# power_tower_mast.net
KiCad netlist of a schematic drawn in EAGLE
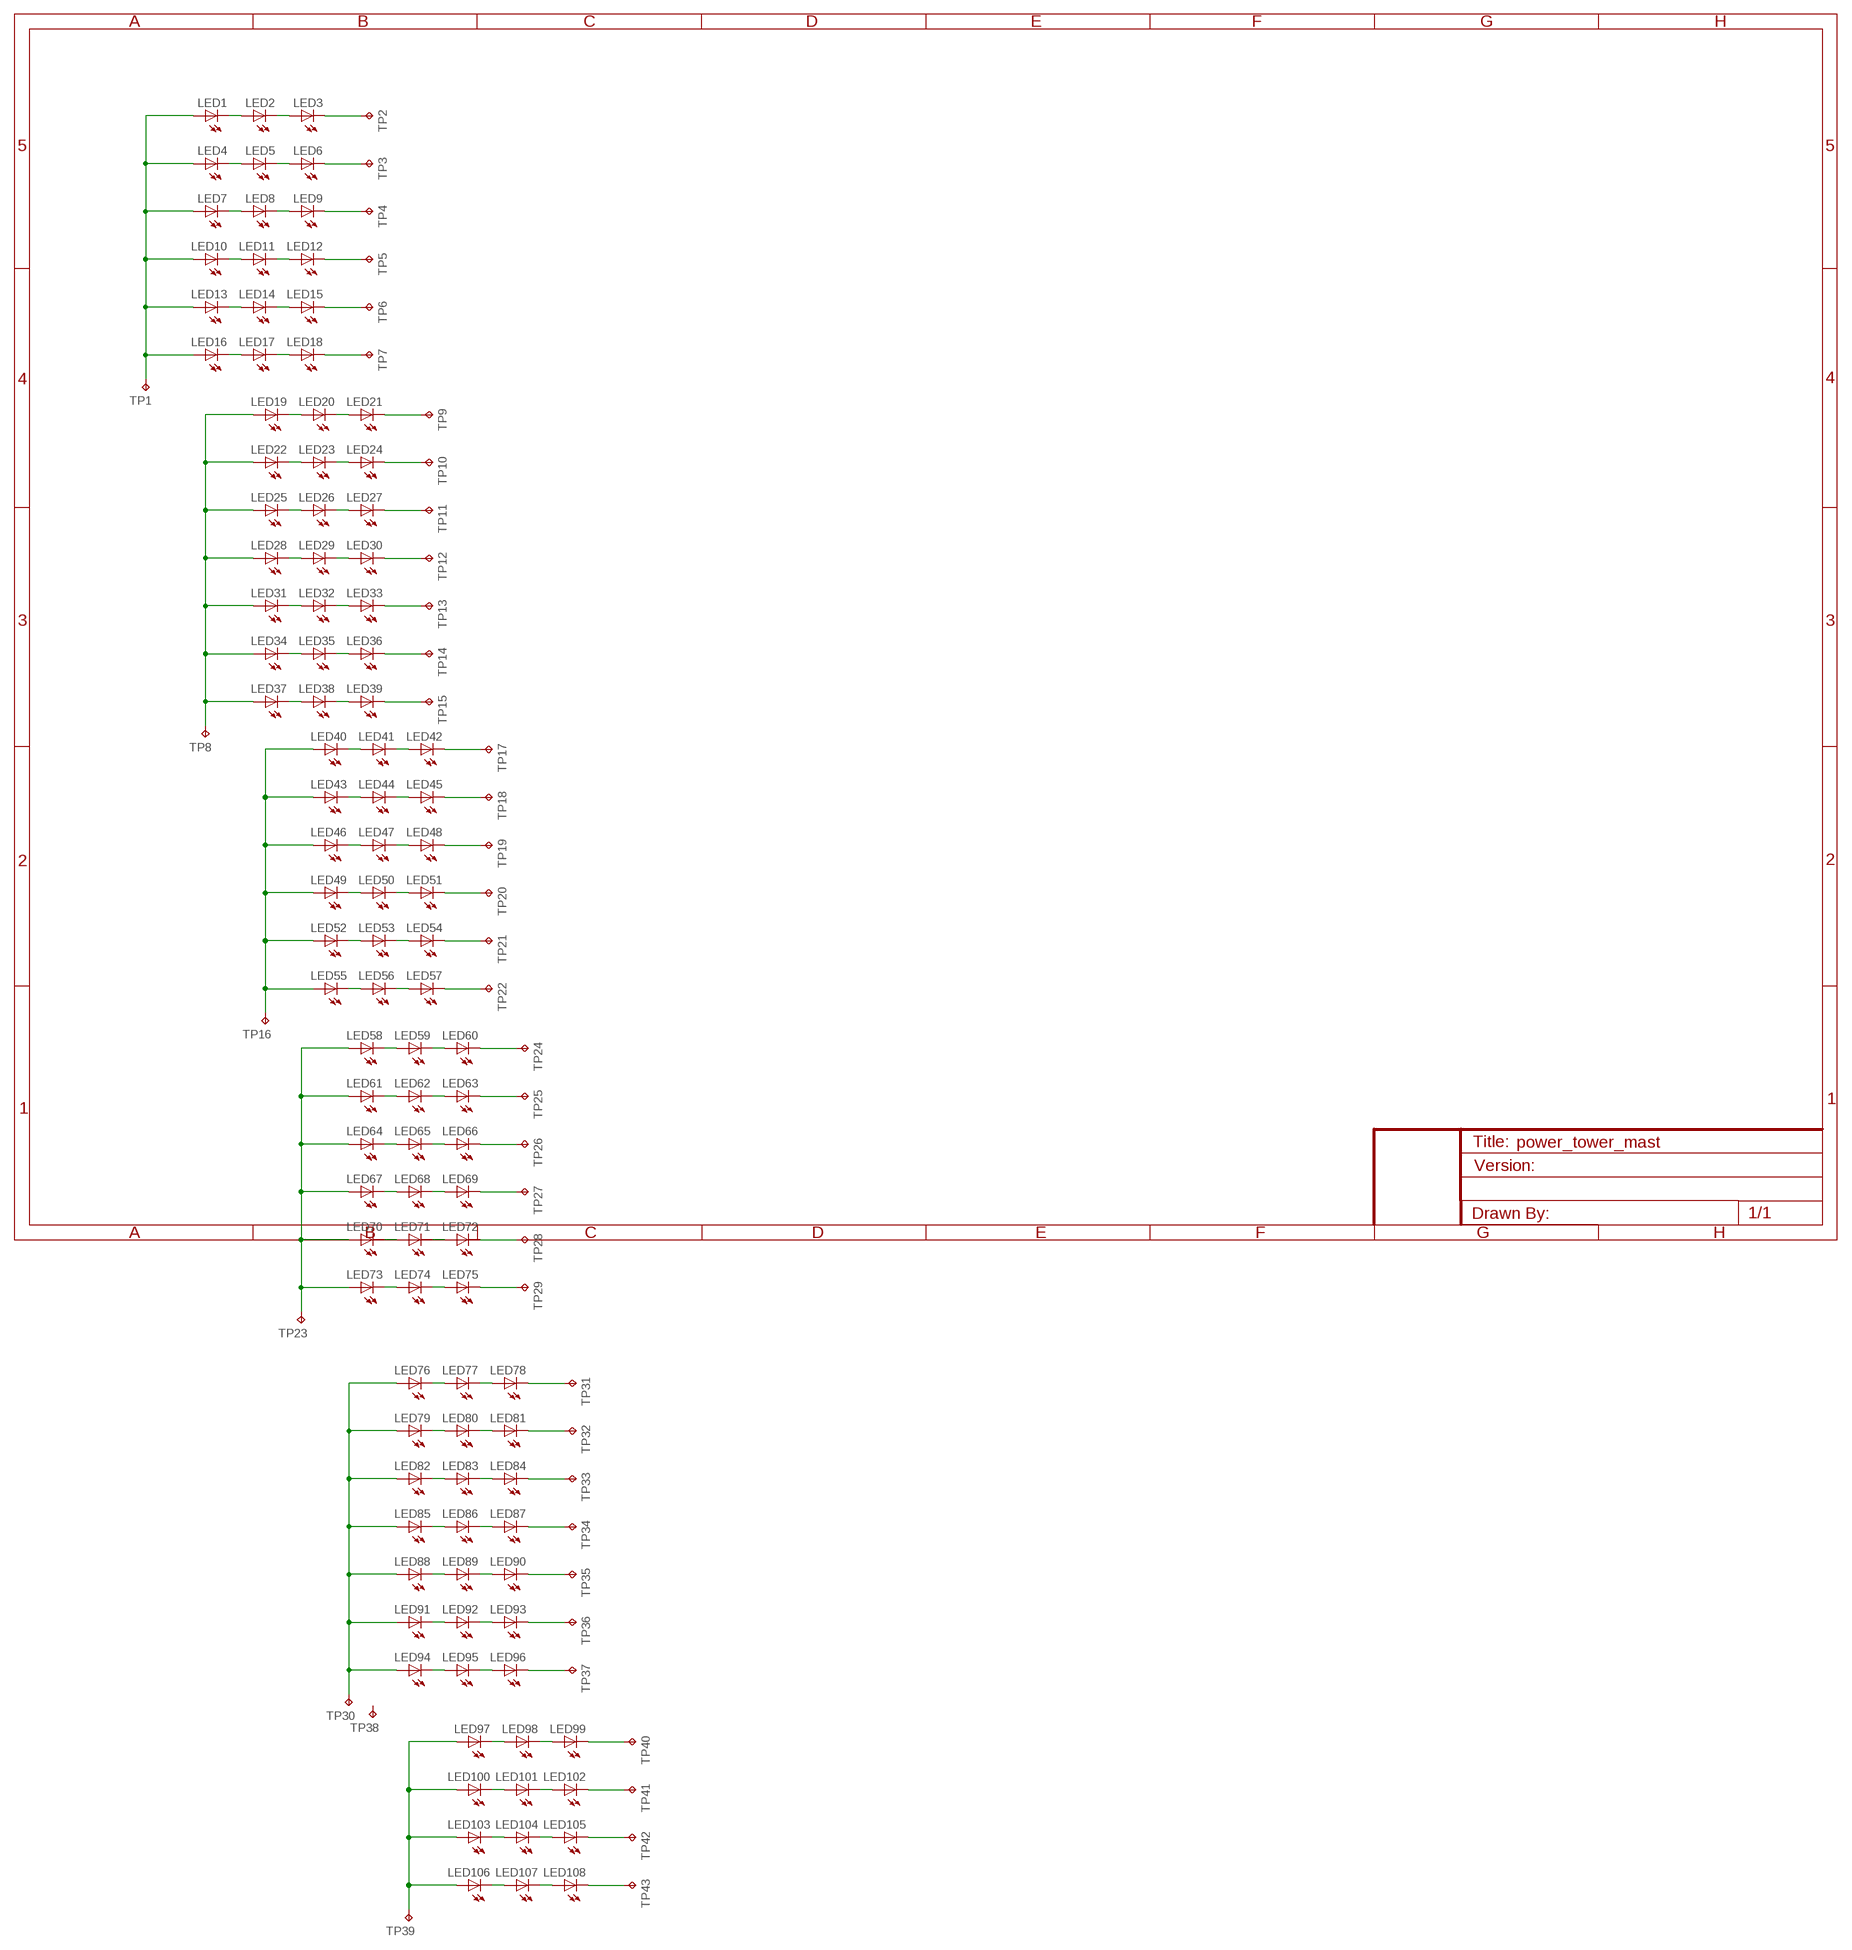
[diagram p0: schematic, sheet 1]

(export (version "E")
  (design (tool "Eeschema 10.0.6"))
  (components
    (comp (ref "LED1")
      (value "LED0805")
      (footprint "eagle-import:LED_0805")
      (libsource (lib "eagle-import") (part "LED0805"))
    )
    (comp (ref "LED2")
      (value "LED0805")
      (footprint "eagle-import:LED_0805")
      (libsource (lib "eagle-import") (part "LED0805"))
    )
    (comp (ref "LED3")
      (value "LED0805")
      (footprint "eagle-import:LED_0805")
      (libsource (lib "eagle-import") (part "LED0805"))
    )
    (comp (ref "LED4")
      (value "LED0805")
      (footprint "eagle-import:LED_0805")
      (libsource (lib "eagle-import") (part "LED0805"))
    )
    (comp (ref "LED5")
      (value "LED0805")
      (footprint "eagle-import:LED_0805")
      (libsource (lib "eagle-import") (part "LED0805"))
    )
    (comp (ref "LED6")
      (value "LED0805")
      (footprint "eagle-import:LED_0805")
      (libsource (lib "eagle-import") (part "LED0805"))
    )
    (comp (ref "LED7")
      (value "LED0805")
      (footprint "eagle-import:LED_0805")
      (libsource (lib "eagle-import") (part "LED0805"))
    )
    (comp (ref "LED8")
      (value "LED0805")
      (footprint "eagle-import:LED_0805")
      (libsource (lib "eagle-import") (part "LED0805"))
    )
    (comp (ref "LED9")
      (value "LED0805")
      (footprint "eagle-import:LED_0805")
      (libsource (lib "eagle-import") (part "LED0805"))
    )
    (comp (ref "LED10")
      (value "LED0805")
      (footprint "eagle-import:LED_0805")
      (libsource (lib "eagle-import") (part "LED0805"))
    )
    (comp (ref "LED11")
      (value "LED0805")
      (footprint "eagle-import:LED_0805")
      (libsource (lib "eagle-import") (part "LED0805"))
    )
    (comp (ref "LED12")
      (value "LED0805")
      (footprint "eagle-import:LED_0805")
      (libsource (lib "eagle-import") (part "LED0805"))
    )
    (comp (ref "LED13")
      (value "LED0805")
      (footprint "eagle-import:LED_0805")
      (libsource (lib "eagle-import") (part "LED0805"))
    )
    (comp (ref "LED14")
      (value "LED0805")
      (footprint "eagle-import:LED_0805")
      (libsource (lib "eagle-import") (part "LED0805"))
    )
    (comp (ref "LED15")
      (value "LED0805")
      (footprint "eagle-import:LED_0805")
      (libsource (lib "eagle-import") (part "LED0805"))
    )
    (comp (ref "LED16")
      (value "LED0805")
      (footprint "eagle-import:LED_0805")
      (libsource (lib "eagle-import") (part "LED0805"))
    )
    (comp (ref "LED17")
      (value "LED0805")
      (footprint "eagle-import:LED_0805")
      (libsource (lib "eagle-import") (part "LED0805"))
    )
    (comp (ref "LED18")
      (value "LED0805")
      (footprint "eagle-import:LED_0805")
      (libsource (lib "eagle-import") (part "LED0805"))
    )
    (comp (ref "LED19")
      (value "LED0805")
      (footprint "eagle-import:LED_0805")
      (libsource (lib "eagle-import") (part "LED0805"))
    )
    (comp (ref "LED20")
      (value "LED0805")
      (footprint "eagle-import:LED_0805")
      (libsource (lib "eagle-import") (part "LED0805"))
    )
    (comp (ref "LED21")
      (value "LED0805")
      (footprint "eagle-import:LED_0805")
      (libsource (lib "eagle-import") (part "LED0805"))
    )
    (comp (ref "LED22")
      (value "LED0805")
      (footprint "eagle-import:LED_0805")
      (libsource (lib "eagle-import") (part "LED0805"))
    )
    (comp (ref "LED23")
      (value "LED0805")
      (footprint "eagle-import:LED_0805")
      (libsource (lib "eagle-import") (part "LED0805"))
    )
    (comp (ref "LED24")
      (value "LED0805")
      (footprint "eagle-import:LED_0805")
      (libsource (lib "eagle-import") (part "LED0805"))
    )
    (comp (ref "LED25")
      (value "LED0805")
      (footprint "eagle-import:LED_0805")
      (libsource (lib "eagle-import") (part "LED0805"))
    )
    (comp (ref "LED26")
      (value "LED0805")
      (footprint "eagle-import:LED_0805")
      (libsource (lib "eagle-import") (part "LED0805"))
    )
    (comp (ref "LED27")
      (value "LED0805")
      (footprint "eagle-import:LED_0805")
      (libsource (lib "eagle-import") (part "LED0805"))
    )
    (comp (ref "LED28")
      (value "LED0805")
      (footprint "eagle-import:LED_0805")
      (libsource (lib "eagle-import") (part "LED0805"))
    )
    (comp (ref "LED29")
      (value "LED0805")
      (footprint "eagle-import:LED_0805")
      (libsource (lib "eagle-import") (part "LED0805"))
    )
    (comp (ref "LED30")
      (value "LED0805")
      (footprint "eagle-import:LED_0805")
      (libsource (lib "eagle-import") (part "LED0805"))
    )
    (comp (ref "LED31")
      (value "LED0805")
      (footprint "eagle-import:LED_0805")
      (libsource (lib "eagle-import") (part "LED0805"))
    )
    (comp (ref "LED32")
      (value "LED0805")
      (footprint "eagle-import:LED_0805")
      (libsource (lib "eagle-import") (part "LED0805"))
    )
    (comp (ref "LED33")
      (value "LED0805")
      (footprint "eagle-import:LED_0805")
      (libsource (lib "eagle-import") (part "LED0805"))
    )
    (comp (ref "LED34")
      (value "LED0805")
      (footprint "eagle-import:LED_0805")
      (libsource (lib "eagle-import") (part "LED0805"))
    )
    (comp (ref "LED35")
      (value "LED0805")
      (footprint "eagle-import:LED_0805")
      (libsource (lib "eagle-import") (part "LED0805"))
    )
    (comp (ref "LED36")
      (value "LED0805")
      (footprint "eagle-import:LED_0805")
      (libsource (lib "eagle-import") (part "LED0805"))
    )
    (comp (ref "LED37")
      (value "LED0805")
      (footprint "eagle-import:LED_0805")
      (libsource (lib "eagle-import") (part "LED0805"))
    )
    (comp (ref "LED38")
      (value "LED0805")
      (footprint "eagle-import:LED_0805")
      (libsource (lib "eagle-import") (part "LED0805"))
    )
    (comp (ref "LED39")
      (value "LED0805")
      (footprint "eagle-import:LED_0805")
      (libsource (lib "eagle-import") (part "LED0805"))
    )
    (comp (ref "LED40")
      (value "LED0805")
      (footprint "eagle-import:LED_0805")
      (libsource (lib "eagle-import") (part "LED0805"))
    )
    (comp (ref "LED41")
      (value "LED0805")
      (footprint "eagle-import:LED_0805")
      (libsource (lib "eagle-import") (part "LED0805"))
    )
    (comp (ref "LED42")
      (value "LED0805")
      (footprint "eagle-import:LED_0805")
      (libsource (lib "eagle-import") (part "LED0805"))
    )
    (comp (ref "LED43")
      (value "LED0805")
      (footprint "eagle-import:LED_0805")
      (libsource (lib "eagle-import") (part "LED0805"))
    )
    (comp (ref "LED44")
      (value "LED0805")
      (footprint "eagle-import:LED_0805")
      (libsource (lib "eagle-import") (part "LED0805"))
    )
    (comp (ref "LED45")
      (value "LED0805")
      (footprint "eagle-import:LED_0805")
      (libsource (lib "eagle-import") (part "LED0805"))
    )
    (comp (ref "LED46")
      (value "LED0805")
      (footprint "eagle-import:LED_0805")
      (libsource (lib "eagle-import") (part "LED0805"))
    )
    (comp (ref "LED47")
      (value "LED0805")
      (footprint "eagle-import:LED_0805")
      (libsource (lib "eagle-import") (part "LED0805"))
    )
    (comp (ref "LED48")
      (value "LED0805")
      (footprint "eagle-import:LED_0805")
      (libsource (lib "eagle-import") (part "LED0805"))
    )
    (comp (ref "LED49")
      (value "LED0805")
      (footprint "eagle-import:LED_0805")
      (libsource (lib "eagle-import") (part "LED0805"))
    )
    (comp (ref "LED50")
      (value "LED0805")
      (footprint "eagle-import:LED_0805")
      (libsource (lib "eagle-import") (part "LED0805"))
    )
    (comp (ref "LED51")
      (value "LED0805")
      (footprint "eagle-import:LED_0805")
      (libsource (lib "eagle-import") (part "LED0805"))
    )
    (comp (ref "LED52")
      (value "LED0805")
      (footprint "eagle-import:LED_0805")
      (libsource (lib "eagle-import") (part "LED0805"))
    )
    (comp (ref "LED53")
      (value "LED0805")
      (footprint "eagle-import:LED_0805")
      (libsource (lib "eagle-import") (part "LED0805"))
    )
    (comp (ref "LED54")
      (value "LED0805")
      (footprint "eagle-import:LED_0805")
      (libsource (lib "eagle-import") (part "LED0805"))
    )
    (comp (ref "LED55")
      (value "LED0805")
      (footprint "eagle-import:LED_0805")
      (libsource (lib "eagle-import") (part "LED0805"))
    )
    (comp (ref "LED56")
      (value "LED0805")
      (footprint "eagle-import:LED_0805")
      (libsource (lib "eagle-import") (part "LED0805"))
    )
    (comp (ref "LED57")
      (value "LED0805")
      (footprint "eagle-import:LED_0805")
      (libsource (lib "eagle-import") (part "LED0805"))
    )
    (comp (ref "LED58")
      (value "LED0805")
      (footprint "eagle-import:LED_0805")
      (libsource (lib "eagle-import") (part "LED0805"))
    )
    (comp (ref "LED59")
      (value "LED0805")
      (footprint "eagle-import:LED_0805")
      (libsource (lib "eagle-import") (part "LED0805"))
    )
    (comp (ref "LED60")
      (value "LED0805")
      (footprint "eagle-import:LED_0805")
      (libsource (lib "eagle-import") (part "LED0805"))
    )
    (comp (ref "LED61")
      (value "LED0805")
      (footprint "eagle-import:LED_0805")
      (libsource (lib "eagle-import") (part "LED0805"))
    )
    (comp (ref "LED62")
      (value "LED0805")
      (footprint "eagle-import:LED_0805")
      (libsource (lib "eagle-import") (part "LED0805"))
    )
    (comp (ref "LED63")
      (value "LED0805")
      (footprint "eagle-import:LED_0805")
      (libsource (lib "eagle-import") (part "LED0805"))
    )
    (comp (ref "LED64")
      (value "LED0805")
      (footprint "eagle-import:LED_0805")
      (libsource (lib "eagle-import") (part "LED0805"))
    )
    (comp (ref "LED65")
      (value "LED0805")
      (footprint "eagle-import:LED_0805")
      (libsource (lib "eagle-import") (part "LED0805"))
    )
    (comp (ref "LED66")
      (value "LED0805")
      (footprint "eagle-import:LED_0805")
      (libsource (lib "eagle-import") (part "LED0805"))
    )
    (comp (ref "LED67")
      (value "LED0805")
      (footprint "eagle-import:LED_0805")
      (libsource (lib "eagle-import") (part "LED0805"))
    )
    (comp (ref "LED68")
      (value "LED0805")
      (footprint "eagle-import:LED_0805")
      (libsource (lib "eagle-import") (part "LED0805"))
    )
    (comp (ref "LED69")
      (value "LED0805")
      (footprint "eagle-import:LED_0805")
      (libsource (lib "eagle-import") (part "LED0805"))
    )
    (comp (ref "LED70")
      (value "LED0805")
      (footprint "eagle-import:LED_0805")
      (libsource (lib "eagle-import") (part "LED0805"))
    )
    (comp (ref "LED71")
      (value "LED0805")
      (footprint "eagle-import:LED_0805")
      (libsource (lib "eagle-import") (part "LED0805"))
    )
    (comp (ref "LED72")
      (value "LED0805")
      (footprint "eagle-import:LED_0805")
      (libsource (lib "eagle-import") (part "LED0805"))
    )
    (comp (ref "LED73")
      (value "LED0805")
      (footprint "eagle-import:LED_0805")
      (libsource (lib "eagle-import") (part "LED0805"))
    )
    (comp (ref "LED74")
      (value "LED0805")
      (footprint "eagle-import:LED_0805")
      (libsource (lib "eagle-import") (part "LED0805"))
    )
    (comp (ref "LED75")
      (value "LED0805")
      (footprint "eagle-import:LED_0805")
      (libsource (lib "eagle-import") (part "LED0805"))
    )
    (comp (ref "LED76")
      (value "LED0805")
      (footprint "eagle-import:LED_0805")
      (libsource (lib "eagle-import") (part "LED0805"))
    )
    (comp (ref "LED77")
      (value "LED0805")
      (footprint "eagle-import:LED_0805")
      (libsource (lib "eagle-import") (part "LED0805"))
    )
    (comp (ref "LED78")
      (value "LED0805")
      (footprint "eagle-import:LED_0805")
      (libsource (lib "eagle-import") (part "LED0805"))
    )
    (comp (ref "LED79")
      (value "LED0805")
      (footprint "eagle-import:LED_0805")
      (libsource (lib "eagle-import") (part "LED0805"))
    )
    (comp (ref "LED80")
      (value "LED0805")
      (footprint "eagle-import:LED_0805")
      (libsource (lib "eagle-import") (part "LED0805"))
    )
    (comp (ref "LED81")
      (value "LED0805")
      (footprint "eagle-import:LED_0805")
      (libsource (lib "eagle-import") (part "LED0805"))
    )
    (comp (ref "LED82")
      (value "LED0805")
      (footprint "eagle-import:LED_0805")
      (libsource (lib "eagle-import") (part "LED0805"))
    )
    (comp (ref "LED83")
      (value "LED0805")
      (footprint "eagle-import:LED_0805")
      (libsource (lib "eagle-import") (part "LED0805"))
    )
    (comp (ref "LED84")
      (value "LED0805")
      (footprint "eagle-import:LED_0805")
      (libsource (lib "eagle-import") (part "LED0805"))
    )
    (comp (ref "LED85")
      (value "LED0805")
      (footprint "eagle-import:LED_0805")
      (libsource (lib "eagle-import") (part "LED0805"))
    )
    (comp (ref "LED86")
      (value "LED0805")
      (footprint "eagle-import:LED_0805")
      (libsource (lib "eagle-import") (part "LED0805"))
    )
    (comp (ref "LED87")
      (value "LED0805")
      (footprint "eagle-import:LED_0805")
      (libsource (lib "eagle-import") (part "LED0805"))
    )
    (comp (ref "LED88")
      (value "LED0805")
      (footprint "eagle-import:LED_0805")
      (libsource (lib "eagle-import") (part "LED0805"))
    )
    (comp (ref "LED89")
      (value "LED0805")
      (footprint "eagle-import:LED_0805")
      (libsource (lib "eagle-import") (part "LED0805"))
    )
    (comp (ref "LED90")
      (value "LED0805")
      (footprint "eagle-import:LED_0805")
      (libsource (lib "eagle-import") (part "LED0805"))
    )
    (comp (ref "LED91")
      (value "LED0805")
      (footprint "eagle-import:LED_0805")
      (libsource (lib "eagle-import") (part "LED0805"))
    )
    (comp (ref "LED92")
      (value "LED0805")
      (footprint "eagle-import:LED_0805")
      (libsource (lib "eagle-import") (part "LED0805"))
    )
    (comp (ref "LED93")
      (value "LED0805")
      (footprint "eagle-import:LED_0805")
      (libsource (lib "eagle-import") (part "LED0805"))
    )
    (comp (ref "LED94")
      (value "LED0805")
      (footprint "eagle-import:LED_0805")
      (libsource (lib "eagle-import") (part "LED0805"))
    )
    (comp (ref "LED95")
      (value "LED0805")
      (footprint "eagle-import:LED_0805")
      (libsource (lib "eagle-import") (part "LED0805"))
    )
    (comp (ref "LED96")
      (value "LED0805")
      (footprint "eagle-import:LED_0805")
      (libsource (lib "eagle-import") (part "LED0805"))
    )
    (comp (ref "LED97")
      (value "LED0805")
      (footprint "eagle-import:LED_0805")
      (libsource (lib "eagle-import") (part "LED0805"))
    )
    (comp (ref "LED98")
      (value "LED0805")
      (footprint "eagle-import:LED_0805")
      (libsource (lib "eagle-import") (part "LED0805"))
    )
    (comp (ref "LED99")
      (value "LED0805")
      (footprint "eagle-import:LED_0805")
      (libsource (lib "eagle-import") (part "LED0805"))
    )
    (comp (ref "LED100")
      (value "LED0805")
      (footprint "eagle-import:LED_0805")
      (libsource (lib "eagle-import") (part "LED0805"))
    )
    (comp (ref "LED101")
      (value "LED0805")
      (footprint "eagle-import:LED_0805")
      (libsource (lib "eagle-import") (part "LED0805"))
    )
    (comp (ref "LED102")
      (value "LED0805")
      (footprint "eagle-import:LED_0805")
      (libsource (lib "eagle-import") (part "LED0805"))
    )
    (comp (ref "LED103")
      (value "LED0805")
      (footprint "eagle-import:LED_0805")
      (libsource (lib "eagle-import") (part "LED0805"))
    )
    (comp (ref "LED104")
      (value "LED0805")
      (footprint "eagle-import:LED_0805")
      (libsource (lib "eagle-import") (part "LED0805"))
    )
    (comp (ref "LED105")
      (value "LED0805")
      (footprint "eagle-import:LED_0805")
      (libsource (lib "eagle-import") (part "LED0805"))
    )
    (comp (ref "LED106")
      (value "LED0805")
      (footprint "eagle-import:LED_0805")
      (libsource (lib "eagle-import") (part "LED0805"))
    )
    (comp (ref "LED107")
      (value "LED0805")
      (footprint "eagle-import:LED_0805")
      (libsource (lib "eagle-import") (part "LED0805"))
    )
    (comp (ref "LED108")
      (value "LED0805")
      (footprint "eagle-import:LED_0805")
      (libsource (lib "eagle-import") (part "LED0805"))
    )
    (comp (ref "TP1")
      (value "TEST_POINTPAD1-20")
      (footprint "eagle-import:P1-20")
      (libsource (lib "eagle-import") (part "TEST_POINTPAD1-20"))
    )
    (comp (ref "TP2")
      (value "TEST_POINTPAD1-20")
      (footprint "eagle-import:P1-20")
      (libsource (lib "eagle-import") (part "TEST_POINTPAD1-20"))
    )
    (comp (ref "TP3")
      (value "TEST_POINTPAD1-20")
      (footprint "eagle-import:P1-20")
      (libsource (lib "eagle-import") (part "TEST_POINTPAD1-20"))
    )
    (comp (ref "TP4")
      (value "TEST_POINTPAD1-20")
      (footprint "eagle-import:P1-20")
      (libsource (lib "eagle-import") (part "TEST_POINTPAD1-20"))
    )
    (comp (ref "TP5")
      (value "TEST_POINTPAD1-20")
      (footprint "eagle-import:P1-20")
      (libsource (lib "eagle-import") (part "TEST_POINTPAD1-20"))
    )
    (comp (ref "TP6")
      (value "TEST_POINTPAD1-20")
      (footprint "eagle-import:P1-20")
      (libsource (lib "eagle-import") (part "TEST_POINTPAD1-20"))
    )
    (comp (ref "TP7")
      (value "TEST_POINTPAD1-20")
      (footprint "eagle-import:P1-20")
      (libsource (lib "eagle-import") (part "TEST_POINTPAD1-20"))
    )
    (comp (ref "TP8")
      (value "TEST_POINTPAD1-20")
      (footprint "eagle-import:P1-20")
      (libsource (lib "eagle-import") (part "TEST_POINTPAD1-20"))
    )
    (comp (ref "TP9")
      (value "TEST_POINTPAD1-20")
      (footprint "eagle-import:P1-20")
      (libsource (lib "eagle-import") (part "TEST_POINTPAD1-20"))
    )
    (comp (ref "TP10")
      (value "TEST_POINTPAD1-20")
      (footprint "eagle-import:P1-20")
      (libsource (lib "eagle-import") (part "TEST_POINTPAD1-20"))
    )
    (comp (ref "TP11")
      (value "TEST_POINTPAD1-20")
      (footprint "eagle-import:P1-20")
      (libsource (lib "eagle-import") (part "TEST_POINTPAD1-20"))
    )
    (comp (ref "TP12")
      (value "TEST_POINTPAD1-20")
      (footprint "eagle-import:P1-20")
      (libsource (lib "eagle-import") (part "TEST_POINTPAD1-20"))
    )
    (comp (ref "TP13")
      (value "TEST_POINTPAD1-20")
      (footprint "eagle-import:P1-20")
      (libsource (lib "eagle-import") (part "TEST_POINTPAD1-20"))
    )
    (comp (ref "TP14")
      (value "TEST_POINTPAD1-20")
      (footprint "eagle-import:P1-20")
      (libsource (lib "eagle-import") (part "TEST_POINTPAD1-20"))
    )
    (comp (ref "TP15")
      (value "TEST_POINTPAD1-20")
      (footprint "eagle-import:P1-20")
      (libsource (lib "eagle-import") (part "TEST_POINTPAD1-20"))
    )
    (comp (ref "TP16")
      (value "TEST_POINTPAD1-20")
      (footprint "eagle-import:P1-20")
      (libsource (lib "eagle-import") (part "TEST_POINTPAD1-20"))
    )
    (comp (ref "TP17")
      (value "TEST_POINTPAD1-20")
      (footprint "eagle-import:P1-20")
      (libsource (lib "eagle-import") (part "TEST_POINTPAD1-20"))
    )
    (comp (ref "TP18")
      (value "TEST_POINTPAD1-20")
      (footprint "eagle-import:P1-20")
      (libsource (lib "eagle-import") (part "TEST_POINTPAD1-20"))
    )
    (comp (ref "TP19")
      (value "TEST_POINTPAD1-20")
      (footprint "eagle-import:P1-20")
      (libsource (lib "eagle-import") (part "TEST_POINTPAD1-20"))
    )
    (comp (ref "TP20")
      (value "TEST_POINTPAD1-20")
      (footprint "eagle-import:P1-20")
      (libsource (lib "eagle-import") (part "TEST_POINTPAD1-20"))
    )
    (comp (ref "TP21")
      (value "TEST_POINTPAD1-20")
      (footprint "eagle-import:P1-20")
      (libsource (lib "eagle-import") (part "TEST_POINTPAD1-20"))
    )
    (comp (ref "TP22")
      (value "TEST_POINTPAD1-20")
      (footprint "eagle-import:P1-20")
      (libsource (lib "eagle-import") (part "TEST_POINTPAD1-20"))
    )
    (comp (ref "TP23")
      (value "TEST_POINTPAD1-20")
      (footprint "eagle-import:P1-20")
      (libsource (lib "eagle-import") (part "TEST_POINTPAD1-20"))
    )
    (comp (ref "TP24")
      (value "TEST_POINTPAD1-20")
      (footprint "eagle-import:P1-20")
      (libsource (lib "eagle-import") (part "TEST_POINTPAD1-20"))
    )
    (comp (ref "TP25")
      (value "TEST_POINTPAD1-20")
      (footprint "eagle-import:P1-20")
      (libsource (lib "eagle-import") (part "TEST_POINTPAD1-20"))
    )
    (comp (ref "TP26")
      (value "TEST_POINTPAD1-20")
      (footprint "eagle-import:P1-20")
      (libsource (lib "eagle-import") (part "TEST_POINTPAD1-20"))
    )
    (comp (ref "TP27")
      (value "TEST_POINTPAD1-20")
      (footprint "eagle-import:P1-20")
      (libsource (lib "eagle-import") (part "TEST_POINTPAD1-20"))
    )
    (comp (ref "TP28")
      (value "TEST_POINTPAD1-20")
      (footprint "eagle-import:P1-20")
      (libsource (lib "eagle-import") (part "TEST_POINTPAD1-20"))
    )
    (comp (ref "TP29")
      (value "TEST_POINTPAD1-20")
      (footprint "eagle-import:P1-20")
      (libsource (lib "eagle-import") (part "TEST_POINTPAD1-20"))
    )
    (comp (ref "TP30")
      (value "TEST_POINTPAD1-20")
      (footprint "eagle-import:P1-20")
      (libsource (lib "eagle-import") (part "TEST_POINTPAD1-20"))
    )
    (comp (ref "TP31")
      (value "TEST_POINTPAD1-20")
      (footprint "eagle-import:P1-20")
      (libsource (lib "eagle-import") (part "TEST_POINTPAD1-20"))
    )
    (comp (ref "TP32")
      (value "TEST_POINTPAD1-20")
      (footprint "eagle-import:P1-20")
      (libsource (lib "eagle-import") (part "TEST_POINTPAD1-20"))
    )
    (comp (ref "TP33")
      (value "TEST_POINTPAD1-20")
      (footprint "eagle-import:P1-20")
      (libsource (lib "eagle-import") (part "TEST_POINTPAD1-20"))
    )
    (comp (ref "TP34")
      (value "TEST_POINTPAD1-20")
      (footprint "eagle-import:P1-20")
      (libsource (lib "eagle-import") (part "TEST_POINTPAD1-20"))
    )
    (comp (ref "TP35")
      (value "TEST_POINTPAD1-20")
      (footprint "eagle-import:P1-20")
      (libsource (lib "eagle-import") (part "TEST_POINTPAD1-20"))
    )
    (comp (ref "TP36")
      (value "TEST_POINTPAD1-20")
      (footprint "eagle-import:P1-20")
      (libsource (lib "eagle-import") (part "TEST_POINTPAD1-20"))
    )
    (comp (ref "TP37")
      (value "TEST_POINTPAD1-20")
      (footprint "eagle-import:P1-20")
      (libsource (lib "eagle-import") (part "TEST_POINTPAD1-20"))
    )
    (comp (ref "TP38")
      (value "TEST_POINTPAD1-20")
      (footprint "eagle-import:P1-20")
      (libsource (lib "eagle-import") (part "TEST_POINTPAD1-20"))
    )
    (comp (ref "TP39")
      (value "TEST_POINTPAD1-20")
      (footprint "eagle-import:P1-20")
      (libsource (lib "eagle-import") (part "TEST_POINTPAD1-20"))
    )
    (comp (ref "TP40")
      (value "TEST_POINTPAD1-20")
      (footprint "eagle-import:P1-20")
      (libsource (lib "eagle-import") (part "TEST_POINTPAD1-20"))
    )
    (comp (ref "TP41")
      (value "TEST_POINTPAD1-20")
      (footprint "eagle-import:P1-20")
      (libsource (lib "eagle-import") (part "TEST_POINTPAD1-20"))
    )
    (comp (ref "TP42")
      (value "TEST_POINTPAD1-20")
      (footprint "eagle-import:P1-20")
      (libsource (lib "eagle-import") (part "TEST_POINTPAD1-20"))
    )
    (comp (ref "TP43")
      (value "TEST_POINTPAD1-20")
      (footprint "eagle-import:P1-20")
      (libsource (lib "eagle-import") (part "TEST_POINTPAD1-20"))
    )
  )
  (nets
    (net (code "1") (name "Net-(LED1-PadA)") (class "Default")
      (node (ref "LED1") (pin "A") (pinfunction "A_A") (pintype "passive"))
      (node (ref "LED10") (pin "A") (pinfunction "A_A") (pintype "passive"))
      (node (ref "LED13") (pin "A") (pinfunction "A_A") (pintype "passive"))
      (node (ref "LED16") (pin "A") (pinfunction "A_A") (pintype "passive"))
      (node (ref "LED4") (pin "A") (pinfunction "A_A") (pintype "passive"))
      (node (ref "LED7") (pin "A") (pinfunction "A_A") (pintype "passive"))
      (node (ref "TP1") (pin "TP") (pinfunction "TP_TP") (pintype "input"))
    )
    (net (code "2") (name "Net-(LED1-PadC)") (class "Default")
      (node (ref "LED1") (pin "C") (pinfunction "C_C") (pintype "passive"))
      (node (ref "LED2") (pin "A") (pinfunction "A_A") (pintype "passive"))
    )
    (net (code "3") (name "Net-(LED2-PadC)") (class "Default")
      (node (ref "LED2") (pin "C") (pinfunction "C_C") (pintype "passive"))
      (node (ref "LED3") (pin "A") (pinfunction "A_A") (pintype "passive"))
    )
    (net (code "4") (name "Net-(LED3-PadC)") (class "Default")
      (node (ref "LED3") (pin "C") (pinfunction "C_C") (pintype "passive"))
      (node (ref "TP2") (pin "TP") (pinfunction "TP_TP") (pintype "input"))
    )
    (net (code "5") (name "Net-(LED4-PadC)") (class "Default")
      (node (ref "LED4") (pin "C") (pinfunction "C_C") (pintype "passive"))
      (node (ref "LED5") (pin "A") (pinfunction "A_A") (pintype "passive"))
    )
    (net (code "6") (name "Net-(LED5-PadC)") (class "Default")
      (node (ref "LED5") (pin "C") (pinfunction "C_C") (pintype "passive"))
      (node (ref "LED6") (pin "A") (pinfunction "A_A") (pintype "passive"))
    )
    (net (code "7") (name "Net-(LED6-PadC)") (class "Default")
      (node (ref "LED6") (pin "C") (pinfunction "C_C") (pintype "passive"))
      (node (ref "TP3") (pin "TP") (pinfunction "TP_TP") (pintype "input"))
    )
    (net (code "8") (name "Net-(LED7-PadC)") (class "Default")
      (node (ref "LED7") (pin "C") (pinfunction "C_C") (pintype "passive"))
      (node (ref "LED8") (pin "A") (pinfunction "A_A") (pintype "passive"))
    )
    (net (code "9") (name "Net-(LED8-PadC)") (class "Default")
      (node (ref "LED8") (pin "C") (pinfunction "C_C") (pintype "passive"))
      (node (ref "LED9") (pin "A") (pinfunction "A_A") (pintype "passive"))
    )
    (net (code "10") (name "Net-(LED9-PadC)") (class "Default")
      (node (ref "LED9") (pin "C") (pinfunction "C_C") (pintype "passive"))
      (node (ref "TP4") (pin "TP") (pinfunction "TP_TP") (pintype "input"))
    )
    (net (code "11") (name "Net-(LED10-PadC)") (class "Default")
      (node (ref "LED10") (pin "C") (pinfunction "C_C") (pintype "passive"))
      (node (ref "LED11") (pin "A") (pinfunction "A_A") (pintype "passive"))
    )
    (net (code "12") (name "Net-(LED11-PadC)") (class "Default")
      (node (ref "LED11") (pin "C") (pinfunction "C_C") (pintype "passive"))
      (node (ref "LED12") (pin "A") (pinfunction "A_A") (pintype "passive"))
    )
    (net (code "13") (name "Net-(LED12-PadC)") (class "Default")
      (node (ref "LED12") (pin "C") (pinfunction "C_C") (pintype "passive"))
      (node (ref "TP5") (pin "TP") (pinfunction "TP_TP") (pintype "input"))
    )
    (net (code "14") (name "Net-(LED13-PadC)") (class "Default")
      (node (ref "LED13") (pin "C") (pinfunction "C_C") (pintype "passive"))
      (node (ref "LED14") (pin "A") (pinfunction "A_A") (pintype "passive"))
    )
    (net (code "15") (name "Net-(LED14-PadC)") (class "Default")
      (node (ref "LED14") (pin "C") (pinfunction "C_C") (pintype "passive"))
      (node (ref "LED15") (pin "A") (pinfunction "A_A") (pintype "passive"))
    )
    (net (code "16") (name "Net-(LED15-PadC)") (class "Default")
      (node (ref "LED15") (pin "C") (pinfunction "C_C") (pintype "passive"))
      (node (ref "TP6") (pin "TP") (pinfunction "TP_TP") (pintype "input"))
    )
    (net (code "17") (name "Net-(LED16-PadC)") (class "Default")
      (node (ref "LED16") (pin "C") (pinfunction "C_C") (pintype "passive"))
      (node (ref "LED17") (pin "A") (pinfunction "A_A") (pintype "passive"))
    )
    (net (code "18") (name "Net-(LED17-PadC)") (class "Default")
      (node (ref "LED17") (pin "C") (pinfunction "C_C") (pintype "passive"))
      (node (ref "LED18") (pin "A") (pinfunction "A_A") (pintype "passive"))
    )
    (net (code "19") (name "Net-(LED18-PadC)") (class "Default")
      (node (ref "LED18") (pin "C") (pinfunction "C_C") (pintype "passive"))
      (node (ref "TP7") (pin "TP") (pinfunction "TP_TP") (pintype "input"))
    )
    (net (code "20") (name "Net-(LED19-PadA)") (class "Default")
      (node (ref "LED19") (pin "A") (pinfunction "A_A") (pintype "passive"))
      (node (ref "LED22") (pin "A") (pinfunction "A_A") (pintype "passive"))
      (node (ref "LED25") (pin "A") (pinfunction "A_A") (pintype "passive"))
      (node (ref "LED28") (pin "A") (pinfunction "A_A") (pintype "passive"))
      (node (ref "LED31") (pin "A") (pinfunction "A_A") (pintype "passive"))
      (node (ref "LED34") (pin "A") (pinfunction "A_A") (pintype "passive"))
      (node (ref "LED37") (pin "A") (pinfunction "A_A") (pintype "passive"))
      (node (ref "TP8") (pin "TP") (pinfunction "TP_TP") (pintype "input"))
    )
    (net (code "21") (name "Net-(LED19-PadC)") (class "Default")
      (node (ref "LED19") (pin "C") (pinfunction "C_C") (pintype "passive"))
      (node (ref "LED20") (pin "A") (pinfunction "A_A") (pintype "passive"))
    )
    (net (code "22") (name "Net-(LED20-PadC)") (class "Default")
      (node (ref "LED20") (pin "C") (pinfunction "C_C") (pintype "passive"))
      (node (ref "LED21") (pin "A") (pinfunction "A_A") (pintype "passive"))
    )
    (net (code "23") (name "Net-(LED21-PadC)") (class "Default")
      (node (ref "LED21") (pin "C") (pinfunction "C_C") (pintype "passive"))
      (node (ref "TP9") (pin "TP") (pinfunction "TP_TP") (pintype "input"))
    )
    (net (code "24") (name "Net-(LED22-PadC)") (class "Default")
      (node (ref "LED22") (pin "C") (pinfunction "C_C") (pintype "passive"))
      (node (ref "LED23") (pin "A") (pinfunction "A_A") (pintype "passive"))
    )
    (net (code "25") (name "Net-(LED23-PadC)") (class "Default")
      (node (ref "LED23") (pin "C") (pinfunction "C_C") (pintype "passive"))
      (node (ref "LED24") (pin "A") (pinfunction "A_A") (pintype "passive"))
    )
    (net (code "26") (name "Net-(LED24-PadC)") (class "Default")
      (node (ref "LED24") (pin "C") (pinfunction "C_C") (pintype "passive"))
      (node (ref "TP10") (pin "TP") (pinfunction "TP_TP") (pintype "input"))
    )
    (net (code "27") (name "Net-(LED25-PadC)") (class "Default")
      (node (ref "LED25") (pin "C") (pinfunction "C_C") (pintype "passive"))
      (node (ref "LED26") (pin "A") (pinfunction "A_A") (pintype "passive"))
    )
    (net (code "28") (name "Net-(LED26-PadC)") (class "Default")
      (node (ref "LED26") (pin "C") (pinfunction "C_C") (pintype "passive"))
      (node (ref "LED27") (pin "A") (pinfunction "A_A") (pintype "passive"))
    )
    (net (code "29") (name "Net-(LED27-PadC)") (class "Default")
      (node (ref "LED27") (pin "C") (pinfunction "C_C") (pintype "passive"))
      (node (ref "TP11") (pin "TP") (pinfunction "TP_TP") (pintype "input"))
    )
    (net (code "30") (name "Net-(LED28-PadC)") (class "Default")
      (node (ref "LED28") (pin "C") (pinfunction "C_C") (pintype "passive"))
      (node (ref "LED29") (pin "A") (pinfunction "A_A") (pintype "passive"))
    )
    (net (code "31") (name "Net-(LED29-PadC)") (class "Default")
      (node (ref "LED29") (pin "C") (pinfunction "C_C") (pintype "passive"))
      (node (ref "LED30") (pin "A") (pinfunction "A_A") (pintype "passive"))
    )
    (net (code "32") (name "Net-(LED30-PadC)") (class "Default")
      (node (ref "LED30") (pin "C") (pinfunction "C_C") (pintype "passive"))
      (node (ref "TP12") (pin "TP") (pinfunction "TP_TP") (pintype "input"))
    )
    (net (code "33") (name "Net-(LED31-PadC)") (class "Default")
      (node (ref "LED31") (pin "C") (pinfunction "C_C") (pintype "passive"))
      (node (ref "LED32") (pin "A") (pinfunction "A_A") (pintype "passive"))
    )
    (net (code "34") (name "Net-(LED32-PadC)") (class "Default")
      (node (ref "LED32") (pin "C") (pinfunction "C_C") (pintype "passive"))
      (node (ref "LED33") (pin "A") (pinfunction "A_A") (pintype "passive"))
    )
    (net (code "35") (name "Net-(LED33-PadC)") (class "Default")
      (node (ref "LED33") (pin "C") (pinfunction "C_C") (pintype "passive"))
      (node (ref "TP13") (pin "TP") (pinfunction "TP_TP") (pintype "input"))
    )
    (net (code "36") (name "Net-(LED34-PadC)") (class "Default")
      (node (ref "LED34") (pin "C") (pinfunction "C_C") (pintype "passive"))
      (node (ref "LED35") (pin "A") (pinfunction "A_A") (pintype "passive"))
    )
    (net (code "37") (name "Net-(LED35-PadC)") (class "Default")
      (node (ref "LED35") (pin "C") (pinfunction "C_C") (pintype "passive"))
      (node (ref "LED36") (pin "A") (pinfunction "A_A") (pintype "passive"))
    )
    (net (code "38") (name "Net-(LED36-PadC)") (class "Default")
      (node (ref "LED36") (pin "C") (pinfunction "C_C") (pintype "passive"))
      (node (ref "TP14") (pin "TP") (pinfunction "TP_TP") (pintype "input"))
    )
    (net (code "39") (name "Net-(LED37-PadC)") (class "Default")
      (node (ref "LED37") (pin "C") (pinfunction "C_C") (pintype "passive"))
      (node (ref "LED38") (pin "A") (pinfunction "A_A") (pintype "passive"))
    )
    (net (code "40") (name "Net-(LED38-PadC)") (class "Default")
      (node (ref "LED38") (pin "C") (pinfunction "C_C") (pintype "passive"))
      (node (ref "LED39") (pin "A") (pinfunction "A_A") (pintype "passive"))
    )
    (net (code "41") (name "Net-(LED39-PadC)") (class "Default")
      (node (ref "LED39") (pin "C") (pinfunction "C_C") (pintype "passive"))
      (node (ref "TP15") (pin "TP") (pinfunction "TP_TP") (pintype "input"))
    )
    (net (code "42") (name "Net-(LED40-PadA)") (class "Default")
      (node (ref "LED40") (pin "A") (pinfunction "A_A") (pintype "passive"))
      (node (ref "LED43") (pin "A") (pinfunction "A_A") (pintype "passive"))
      (node (ref "LED46") (pin "A") (pinfunction "A_A") (pintype "passive"))
      (node (ref "LED49") (pin "A") (pinfunction "A_A") (pintype "passive"))
      (node (ref "LED52") (pin "A") (pinfunction "A_A") (pintype "passive"))
      (node (ref "LED55") (pin "A") (pinfunction "A_A") (pintype "passive"))
      (node (ref "TP16") (pin "TP") (pinfunction "TP_TP") (pintype "input"))
    )
    (net (code "43") (name "Net-(LED40-PadC)") (class "Default")
      (node (ref "LED40") (pin "C") (pinfunction "C_C") (pintype "passive"))
      (node (ref "LED41") (pin "A") (pinfunction "A_A") (pintype "passive"))
    )
    (net (code "44") (name "Net-(LED41-PadC)") (class "Default")
      (node (ref "LED41") (pin "C") (pinfunction "C_C") (pintype "passive"))
      (node (ref "LED42") (pin "A") (pinfunction "A_A") (pintype "passive"))
    )
    (net (code "45") (name "Net-(LED42-PadC)") (class "Default")
      (node (ref "LED42") (pin "C") (pinfunction "C_C") (pintype "passive"))
      (node (ref "TP17") (pin "TP") (pinfunction "TP_TP") (pintype "input"))
    )
    (net (code "46") (name "Net-(LED43-PadC)") (class "Default")
      (node (ref "LED43") (pin "C") (pinfunction "C_C") (pintype "passive"))
      (node (ref "LED44") (pin "A") (pinfunction "A_A") (pintype "passive"))
    )
    (net (code "47") (name "Net-(LED44-PadC)") (class "Default")
      (node (ref "LED44") (pin "C") (pinfunction "C_C") (pintype "passive"))
      (node (ref "LED45") (pin "A") (pinfunction "A_A") (pintype "passive"))
    )
    (net (code "48") (name "Net-(LED45-PadC)") (class "Default")
      (node (ref "LED45") (pin "C") (pinfunction "C_C") (pintype "passive"))
      (node (ref "TP18") (pin "TP") (pinfunction "TP_TP") (pintype "input"))
    )
    (net (code "49") (name "Net-(LED46-PadC)") (class "Default")
      (node (ref "LED46") (pin "C") (pinfunction "C_C") (pintype "passive"))
      (node (ref "LED47") (pin "A") (pinfunction "A_A") (pintype "passive"))
    )
    (net (code "50") (name "Net-(LED47-PadC)") (class "Default")
      (node (ref "LED47") (pin "C") (pinfunction "C_C") (pintype "passive"))
      (node (ref "LED48") (pin "A") (pinfunction "A_A") (pintype "passive"))
    )
    (net (code "51") (name "Net-(LED48-PadC)") (class "Default")
      (node (ref "LED48") (pin "C") (pinfunction "C_C") (pintype "passive"))
      (node (ref "TP19") (pin "TP") (pinfunction "TP_TP") (pintype "input"))
    )
    (net (code "52") (name "Net-(LED49-PadC)") (class "Default")
      (node (ref "LED49") (pin "C") (pinfunction "C_C") (pintype "passive"))
      (node (ref "LED50") (pin "A") (pinfunction "A_A") (pintype "passive"))
    )
    (net (code "53") (name "Net-(LED50-PadC)") (class "Default")
      (node (ref "LED50") (pin "C") (pinfunction "C_C") (pintype "passive"))
      (node (ref "LED51") (pin "A") (pinfunction "A_A") (pintype "passive"))
    )
    (net (code "54") (name "Net-(LED51-PadC)") (class "Default")
      (node (ref "LED51") (pin "C") (pinfunction "C_C") (pintype "passive"))
      (node (ref "TP20") (pin "TP") (pinfunction "TP_TP") (pintype "input"))
    )
    (net (code "55") (name "Net-(LED52-PadC)") (class "Default")
      (node (ref "LED52") (pin "C") (pinfunction "C_C") (pintype "passive"))
      (node (ref "LED53") (pin "A") (pinfunction "A_A") (pintype "passive"))
    )
    (net (code "56") (name "Net-(LED53-PadC)") (class "Default")
      (node (ref "LED53") (pin "C") (pinfunction "C_C") (pintype "passive"))
      (node (ref "LED54") (pin "A") (pinfunction "A_A") (pintype "passive"))
    )
    (net (code "57") (name "Net-(LED54-PadC)") (class "Default")
      (node (ref "LED54") (pin "C") (pinfunction "C_C") (pintype "passive"))
      (node (ref "TP21") (pin "TP") (pinfunction "TP_TP") (pintype "input"))
    )
    (net (code "58") (name "Net-(LED55-PadC)") (class "Default")
      (node (ref "LED55") (pin "C") (pinfunction "C_C") (pintype "passive"))
      (node (ref "LED56") (pin "A") (pinfunction "A_A") (pintype "passive"))
    )
    (net (code "59") (name "Net-(LED56-PadC)") (class "Default")
      (node (ref "LED56") (pin "C") (pinfunction "C_C") (pintype "passive"))
      (node (ref "LED57") (pin "A") (pinfunction "A_A") (pintype "passive"))
    )
    (net (code "60") (name "Net-(LED57-PadC)") (class "Default")
      (node (ref "LED57") (pin "C") (pinfunction "C_C") (pintype "passive"))
      (node (ref "TP22") (pin "TP") (pinfunction "TP_TP") (pintype "input"))
    )
    (net (code "61") (name "Net-(LED58-PadA)") (class "Default")
      (node (ref "LED58") (pin "A") (pinfunction "A_A") (pintype "passive"))
      (node (ref "LED61") (pin "A") (pinfunction "A_A") (pintype "passive"))
      (node (ref "LED64") (pin "A") (pinfunction "A_A") (pintype "passive"))
      (node (ref "LED67") (pin "A") (pinfunction "A_A") (pintype "passive"))
      (node (ref "LED70") (pin "A") (pinfunction "A_A") (pintype "passive"))
      (node (ref "LED73") (pin "A") (pinfunction "A_A") (pintype "passive"))
      (node (ref "TP23") (pin "TP") (pinfunction "TP_TP") (pintype "input"))
    )
    (net (code "62") (name "Net-(LED58-PadC)") (class "Default")
      (node (ref "LED58") (pin "C") (pinfunction "C_C") (pintype "passive"))
      (node (ref "LED59") (pin "A") (pinfunction "A_A") (pintype "passive"))
    )
    (net (code "63") (name "Net-(LED59-PadC)") (class "Default")
      (node (ref "LED59") (pin "C") (pinfunction "C_C") (pintype "passive"))
      (node (ref "LED60") (pin "A") (pinfunction "A_A") (pintype "passive"))
    )
    (net (code "64") (name "Net-(LED60-PadC)") (class "Default")
      (node (ref "LED60") (pin "C") (pinfunction "C_C") (pintype "passive"))
      (node (ref "TP24") (pin "TP") (pinfunction "TP_TP") (pintype "input"))
    )
    (net (code "65") (name "Net-(LED61-PadC)") (class "Default")
      (node (ref "LED61") (pin "C") (pinfunction "C_C") (pintype "passive"))
      (node (ref "LED62") (pin "A") (pinfunction "A_A") (pintype "passive"))
    )
    (net (code "66") (name "Net-(LED62-PadC)") (class "Default")
      (node (ref "LED62") (pin "C") (pinfunction "C_C") (pintype "passive"))
      (node (ref "LED63") (pin "A") (pinfunction "A_A") (pintype "passive"))
    )
    (net (code "67") (name "Net-(LED63-PadC)") (class "Default")
      (node (ref "LED63") (pin "C") (pinfunction "C_C") (pintype "passive"))
      (node (ref "TP25") (pin "TP") (pinfunction "TP_TP") (pintype "input"))
    )
    (net (code "68") (name "Net-(LED64-PadC)") (class "Default")
      (node (ref "LED64") (pin "C") (pinfunction "C_C") (pintype "passive"))
      (node (ref "LED65") (pin "A") (pinfunction "A_A") (pintype "passive"))
    )
    (net (code "69") (name "Net-(LED65-PadC)") (class "Default")
      (node (ref "LED65") (pin "C") (pinfunction "C_C") (pintype "passive"))
      (node (ref "LED66") (pin "A") (pinfunction "A_A") (pintype "passive"))
    )
    (net (code "70") (name "Net-(LED66-PadC)") (class "Default")
      (node (ref "LED66") (pin "C") (pinfunction "C_C") (pintype "passive"))
      (node (ref "TP26") (pin "TP") (pinfunction "TP_TP") (pintype "input"))
    )
    (net (code "71") (name "Net-(LED67-PadC)") (class "Default")
      (node (ref "LED67") (pin "C") (pinfunction "C_C") (pintype "passive"))
      (node (ref "LED68") (pin "A") (pinfunction "A_A") (pintype "passive"))
    )
    (net (code "72") (name "Net-(LED68-PadC)") (class "Default")
      (node (ref "LED68") (pin "C") (pinfunction "C_C") (pintype "passive"))
      (node (ref "LED69") (pin "A") (pinfunction "A_A") (pintype "passive"))
    )
    (net (code "73") (name "Net-(LED69-PadC)") (class "Default")
      (node (ref "LED69") (pin "C") (pinfunction "C_C") (pintype "passive"))
      (node (ref "TP27") (pin "TP") (pinfunction "TP_TP") (pintype "input"))
    )
    (net (code "74") (name "Net-(LED70-PadC)") (class "Default")
      (node (ref "LED70") (pin "C") (pinfunction "C_C") (pintype "passive"))
      (node (ref "LED71") (pin "A") (pinfunction "A_A") (pintype "passive"))
    )
    (net (code "75") (name "Net-(LED71-PadC)") (class "Default")
      (node (ref "LED71") (pin "C") (pinfunction "C_C") (pintype "passive"))
      (node (ref "LED72") (pin "A") (pinfunction "A_A") (pintype "passive"))
    )
    (net (code "76") (name "Net-(LED72-PadC)") (class "Default")
      (node (ref "LED72") (pin "C") (pinfunction "C_C") (pintype "passive"))
      (node (ref "TP28") (pin "TP") (pinfunction "TP_TP") (pintype "input"))
    )
    (net (code "77") (name "Net-(LED73-PadC)") (class "Default")
      (node (ref "LED73") (pin "C") (pinfunction "C_C") (pintype "passive"))
      (node (ref "LED74") (pin "A") (pinfunction "A_A") (pintype "passive"))
    )
    (net (code "78") (name "Net-(LED74-PadC)") (class "Default")
      (node (ref "LED74") (pin "C") (pinfunction "C_C") (pintype "passive"))
      (node (ref "LED75") (pin "A") (pinfunction "A_A") (pintype "passive"))
    )
    (net (code "79") (name "Net-(LED75-PadC)") (class "Default")
      (node (ref "LED75") (pin "C") (pinfunction "C_C") (pintype "passive"))
      (node (ref "TP29") (pin "TP") (pinfunction "TP_TP") (pintype "input"))
    )
    (net (code "80") (name "Net-(LED76-PadA)") (class "Default")
      (node (ref "LED76") (pin "A") (pinfunction "A_A") (pintype "passive"))
      (node (ref "LED79") (pin "A") (pinfunction "A_A") (pintype "passive"))
      (node (ref "LED82") (pin "A") (pinfunction "A_A") (pintype "passive"))
      (node (ref "LED85") (pin "A") (pinfunction "A_A") (pintype "passive"))
      (node (ref "LED88") (pin "A") (pinfunction "A_A") (pintype "passive"))
      (node (ref "LED91") (pin "A") (pinfunction "A_A") (pintype "passive"))
      (node (ref "LED94") (pin "A") (pinfunction "A_A") (pintype "passive"))
      (node (ref "TP30") (pin "TP") (pinfunction "TP_TP") (pintype "input"))
    )
    (net (code "81") (name "Net-(LED76-PadC)") (class "Default")
      (node (ref "LED76") (pin "C") (pinfunction "C_C") (pintype "passive"))
      (node (ref "LED77") (pin "A") (pinfunction "A_A") (pintype "passive"))
    )
    (net (code "82") (name "Net-(LED77-PadC)") (class "Default")
      (node (ref "LED77") (pin "C") (pinfunction "C_C") (pintype "passive"))
      (node (ref "LED78") (pin "A") (pinfunction "A_A") (pintype "passive"))
    )
    (net (code "83") (name "Net-(LED78-PadC)") (class "Default")
      (node (ref "LED78") (pin "C") (pinfunction "C_C") (pintype "passive"))
      (node (ref "TP31") (pin "TP") (pinfunction "TP_TP") (pintype "input"))
    )
    (net (code "84") (name "Net-(LED79-PadC)") (class "Default")
      (node (ref "LED79") (pin "C") (pinfunction "C_C") (pintype "passive"))
      (node (ref "LED80") (pin "A") (pinfunction "A_A") (pintype "passive"))
    )
    (net (code "85") (name "Net-(LED80-PadC)") (class "Default")
      (node (ref "LED80") (pin "C") (pinfunction "C_C") (pintype "passive"))
      (node (ref "LED81") (pin "A") (pinfunction "A_A") (pintype "passive"))
    )
    (net (code "86") (name "Net-(LED81-PadC)") (class "Default")
      (node (ref "LED81") (pin "C") (pinfunction "C_C") (pintype "passive"))
      (node (ref "TP32") (pin "TP") (pinfunction "TP_TP") (pintype "input"))
    )
    (net (code "87") (name "Net-(LED82-PadC)") (class "Default")
      (node (ref "LED82") (pin "C") (pinfunction "C_C") (pintype "passive"))
      (node (ref "LED83") (pin "A") (pinfunction "A_A") (pintype "passive"))
    )
    (net (code "88") (name "Net-(LED83-PadC)") (class "Default")
      (node (ref "LED83") (pin "C") (pinfunction "C_C") (pintype "passive"))
      (node (ref "LED84") (pin "A") (pinfunction "A_A") (pintype "passive"))
    )
    (net (code "89") (name "Net-(LED84-PadC)") (class "Default")
      (node (ref "LED84") (pin "C") (pinfunction "C_C") (pintype "passive"))
      (node (ref "TP33") (pin "TP") (pinfunction "TP_TP") (pintype "input"))
    )
    (net (code "90") (name "Net-(LED85-PadC)") (class "Default")
      (node (ref "LED85") (pin "C") (pinfunction "C_C") (pintype "passive"))
      (node (ref "LED86") (pin "A") (pinfunction "A_A") (pintype "passive"))
    )
    (net (code "91") (name "Net-(LED86-PadC)") (class "Default")
      (node (ref "LED86") (pin "C") (pinfunction "C_C") (pintype "passive"))
      (node (ref "LED87") (pin "A") (pinfunction "A_A") (pintype "passive"))
    )
    (net (code "92") (name "Net-(LED87-PadC)") (class "Default")
      (node (ref "LED87") (pin "C") (pinfunction "C_C") (pintype "passive"))
      (node (ref "TP34") (pin "TP") (pinfunction "TP_TP") (pintype "input"))
    )
    (net (code "93") (name "Net-(LED88-PadC)") (class "Default")
      (node (ref "LED88") (pin "C") (pinfunction "C_C") (pintype "passive"))
      (node (ref "LED89") (pin "A") (pinfunction "A_A") (pintype "passive"))
    )
    (net (code "94") (name "Net-(LED89-PadC)") (class "Default")
      (node (ref "LED89") (pin "C") (pinfunction "C_C") (pintype "passive"))
      (node (ref "LED90") (pin "A") (pinfunction "A_A") (pintype "passive"))
    )
    (net (code "95") (name "Net-(LED90-PadC)") (class "Default")
      (node (ref "LED90") (pin "C") (pinfunction "C_C") (pintype "passive"))
      (node (ref "TP35") (pin "TP") (pinfunction "TP_TP") (pintype "input"))
    )
    (net (code "96") (name "Net-(LED91-PadC)") (class "Default")
      (node (ref "LED91") (pin "C") (pinfunction "C_C") (pintype "passive"))
      (node (ref "LED92") (pin "A") (pinfunction "A_A") (pintype "passive"))
    )
    (net (code "97") (name "Net-(LED92-PadC)") (class "Default")
      (node (ref "LED92") (pin "C") (pinfunction "C_C") (pintype "passive"))
      (node (ref "LED93") (pin "A") (pinfunction "A_A") (pintype "passive"))
    )
    (net (code "98") (name "Net-(LED93-PadC)") (class "Default")
      (node (ref "LED93") (pin "C") (pinfunction "C_C") (pintype "passive"))
      (node (ref "TP36") (pin "TP") (pinfunction "TP_TP") (pintype "input"))
    )
    (net (code "99") (name "Net-(LED94-PadC)") (class "Default")
      (node (ref "LED94") (pin "C") (pinfunction "C_C") (pintype "passive"))
      (node (ref "LED95") (pin "A") (pinfunction "A_A") (pintype "passive"))
    )
    (net (code "100") (name "Net-(LED95-PadC)") (class "Default")
      (node (ref "LED95") (pin "C") (pinfunction "C_C") (pintype "passive"))
      (node (ref "LED96") (pin "A") (pinfunction "A_A") (pintype "passive"))
    )
    (net (code "101") (name "Net-(LED96-PadC)") (class "Default")
      (node (ref "LED96") (pin "C") (pinfunction "C_C") (pintype "passive"))
      (node (ref "TP37") (pin "TP") (pinfunction "TP_TP") (pintype "input"))
    )
    (net (code "102") (name "Net-(LED97-PadC)") (class "Default")
      (node (ref "LED97") (pin "C") (pinfunction "C_C") (pintype "passive"))
      (node (ref "LED98") (pin "A") (pinfunction "A_A") (pintype "passive"))
    )
    (net (code "103") (name "Net-(LED98-PadC)") (class "Default")
      (node (ref "LED98") (pin "C") (pinfunction "C_C") (pintype "passive"))
      (node (ref "LED99") (pin "A") (pinfunction "A_A") (pintype "passive"))
    )
    (net (code "104") (name "Net-(LED99-PadC)") (class "Default")
      (node (ref "LED99") (pin "C") (pinfunction "C_C") (pintype "passive"))
      (node (ref "TP40") (pin "TP") (pinfunction "TP_TP") (pintype "input"))
    )
    (net (code "105") (name "Net-(LED100-PadA)") (class "Default")
      (node (ref "LED100") (pin "A") (pinfunction "A_A") (pintype "passive"))
      (node (ref "LED103") (pin "A") (pinfunction "A_A") (pintype "passive"))
      (node (ref "LED106") (pin "A") (pinfunction "A_A") (pintype "passive"))
      (node (ref "LED97") (pin "A") (pinfunction "A_A") (pintype "passive"))
      (node (ref "TP39") (pin "TP") (pinfunction "TP_TP") (pintype "input"))
    )
    (net (code "106") (name "Net-(LED100-PadC)") (class "Default")
      (node (ref "LED100") (pin "C") (pinfunction "C_C") (pintype "passive"))
      (node (ref "LED101") (pin "A") (pinfunction "A_A") (pintype "passive"))
    )
    (net (code "107") (name "Net-(LED101-PadC)") (class "Default")
      (node (ref "LED101") (pin "C") (pinfunction "C_C") (pintype "passive"))
      (node (ref "LED102") (pin "A") (pinfunction "A_A") (pintype "passive"))
    )
    (net (code "108") (name "Net-(LED102-PadC)") (class "Default")
      (node (ref "LED102") (pin "C") (pinfunction "C_C") (pintype "passive"))
      (node (ref "TP41") (pin "TP") (pinfunction "TP_TP") (pintype "input"))
    )
    (net (code "109") (name "Net-(LED103-PadC)") (class "Default")
      (node (ref "LED103") (pin "C") (pinfunction "C_C") (pintype "passive"))
      (node (ref "LED104") (pin "A") (pinfunction "A_A") (pintype "passive"))
    )
    (net (code "110") (name "Net-(LED104-PadC)") (class "Default")
      (node (ref "LED104") (pin "C") (pinfunction "C_C") (pintype "passive"))
      (node (ref "LED105") (pin "A") (pinfunction "A_A") (pintype "passive"))
    )
    (net (code "111") (name "Net-(LED105-PadC)") (class "Default")
      (node (ref "LED105") (pin "C") (pinfunction "C_C") (pintype "passive"))
      (node (ref "TP42") (pin "TP") (pinfunction "TP_TP") (pintype "input"))
    )
    (net (code "112") (name "Net-(LED106-PadC)") (class "Default")
      (node (ref "LED106") (pin "C") (pinfunction "C_C") (pintype "passive"))
      (node (ref "LED107") (pin "A") (pinfunction "A_A") (pintype "passive"))
    )
    (net (code "113") (name "Net-(LED107-PadC)") (class "Default")
      (node (ref "LED107") (pin "C") (pinfunction "C_C") (pintype "passive"))
      (node (ref "LED108") (pin "A") (pinfunction "A_A") (pintype "passive"))
    )
    (net (code "114") (name "Net-(LED108-PadC)") (class "Default")
      (node (ref "LED108") (pin "C") (pinfunction "C_C") (pintype "passive"))
      (node (ref "TP43") (pin "TP") (pinfunction "TP_TP") (pintype "input"))
    )
    (net (code "115") (name "unconnected-(TP38-PadTP)") (class "Default")
      (node (ref "TP38") (pin "TP") (pinfunction "TP_TP") (pintype "input"))
    )
  )
)
